# mother1.net
KiCad netlist of a schematic drawn in Altium Designer
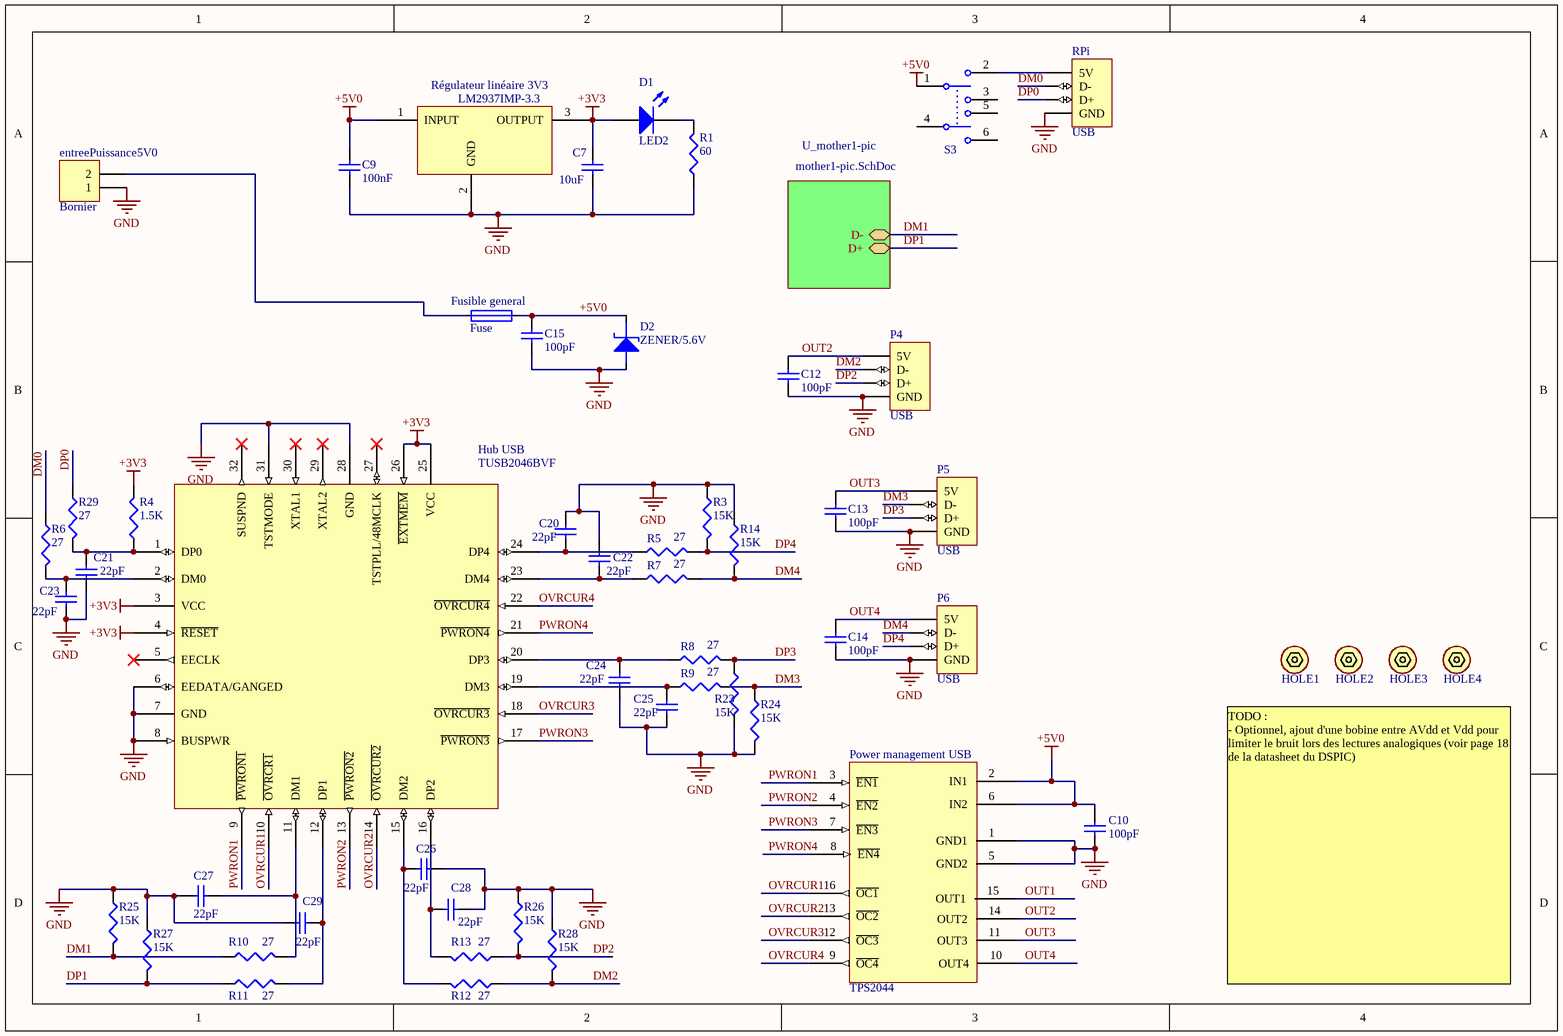
[diagram p0: mother1.SchDoc]

(export (version "E")
  (design (tool "Eeschema 10.0.6"))
  (components
    (comp (ref "C7")
      (value "10uF")
      (footprint "C0805C")
      (description "Capacitor")
      (fields (field (name "Comment") "CAP") (field (name "PUBLISHER") "Altium Limited"))
      (libsource (lib "7Robot") (part "CAP"))
    )
    (comp (ref "C9")
      (value "100nF")
      (footprint "C0805C")
      (description "Capacitor")
      (fields (field (name "Comment") "CAP") (field (name "PUBLISHER") "Altium Limited"))
      (libsource (lib "7Robot") (part "CAP"))
    )
    (comp (ref "C10")
      (value "100pF")
      (footprint "C0805C")
      (description "Capacitor")
      (fields (field (name "Comment") "CAP") (field (name "PUBLISHER") "Altium Limited"))
      (libsource (lib "7Robot") (part "CAP"))
    )
    (comp (ref "C12")
      (value "100pF")
      (footprint "C0805C")
      (description "Capacitor")
      (fields (field (name "Comment") "CAP") (field (name "PUBLISHER") "Altium Limited"))
      (libsource (lib "7Robot") (part "CAP"))
    )
    (comp (ref "C13")
      (value "100pF")
      (footprint "C0805C")
      (description "Capacitor")
      (fields (field (name "Comment") "CAP") (field (name "PUBLISHER") "Altium Limited"))
      (libsource (lib "7Robot") (part "CAP"))
    )
    (comp (ref "C14")
      (value "100pF")
      (footprint "C0805C")
      (description "Capacitor")
      (fields (field (name "Comment") "CAP") (field (name "PUBLISHER") "Altium Limited"))
      (libsource (lib "7Robot") (part "CAP"))
    )
    (comp (ref "C15")
      (value "100pF")
      (footprint "C0805C")
      (description "Capacitor")
      (fields (field (name "Comment") "CAP") (field (name "PUBLISHER") "Altium Limited"))
      (libsource (lib "7Robot") (part "CAP"))
    )
    (comp (ref "C20")
      (value "22pF")
      (footprint "C0805C")
      (description "Capacitor")
      (fields (field (name "Comment") "CAP") (field (name "PUBLISHER") "Altium Limited"))
      (libsource (lib "7Robot") (part "CAP"))
    )
    (comp (ref "C21")
      (value "22pF")
      (footprint "C0805C")
      (description "Capacitor")
      (fields (field (name "Comment") "CAP") (field (name "PUBLISHER") "Altium Limited"))
      (libsource (lib "7Robot") (part "CAP"))
    )
    (comp (ref "C22")
      (value "22pF")
      (footprint "C0805C")
      (description "Capacitor")
      (fields (field (name "Comment") "CAP") (field (name "PUBLISHER") "Altium Limited"))
      (libsource (lib "7Robot") (part "CAP"))
    )
    (comp (ref "C23")
      (value "22pF")
      (footprint "C0805C")
      (description "Capacitor")
      (fields (field (name "Comment") "CAP") (field (name "PUBLISHER") "Altium Limited"))
      (libsource (lib "7Robot") (part "CAP"))
    )
    (comp (ref "C24")
      (value "22pF")
      (footprint "C0805C")
      (description "Capacitor")
      (fields (field (name "Comment") "CAP") (field (name "PUBLISHER") "Altium Limited"))
      (libsource (lib "7Robot") (part "CAP"))
    )
    (comp (ref "C25")
      (value "22pF")
      (footprint "C0805C")
      (description "Capacitor")
      (fields (field (name "Comment") "CAP") (field (name "PUBLISHER") "Altium Limited"))
      (libsource (lib "7Robot") (part "CAP"))
    )
    (comp (ref "C26")
      (value "22pF")
      (footprint "C0805C")
      (description "Capacitor")
      (fields (field (name "Comment") "CAP") (field (name "PUBLISHER") "Altium Limited"))
      (libsource (lib "7Robot") (part "CAP"))
    )
    (comp (ref "C27")
      (value "22pF")
      (footprint "C0805C")
      (description "Capacitor")
      (fields (field (name "Comment") "CAP") (field (name "PUBLISHER") "Altium Limited"))
      (libsource (lib "7Robot") (part "CAP"))
    )
    (comp (ref "C28")
      (value "22pF")
      (footprint "C0805C")
      (description "Capacitor")
      (fields (field (name "Comment") "CAP") (field (name "PUBLISHER") "Altium Limited"))
      (libsource (lib "7Robot") (part "CAP"))
    )
    (comp (ref "C29")
      (value "22pF")
      (footprint "C0805C")
      (description "Capacitor")
      (fields (field (name "Comment") "CAP") (field (name "PUBLISHER") "Altium Limited"))
      (libsource (lib "7Robot") (part "CAP"))
    )
    (comp (ref "D1")
      (value "LED2")
      (footprint "LED1206G")
      (description "Typical RED, GREEN, YELLOW, AMBER GaAs LED")
      (fields (field (name "PUBLISHER") "Altium Limited"))
      (libsource (lib "7Robot") (part "LED2"))
    )
    (comp (ref "D2")
      (value "ZENER/5.6V")
      (footprint "DSO-C2/X1.8")
      (description "ZENER")
      (libsource (lib "7Robot") (part "ZENER"))
    )
    (comp (ref "entreePuissance5V0")
      (value "Bornier")
      (footprint "Bornier male coude 2 voies")
      (description "Header, 2-Pin")
      (fields (field (name "PUBLISHER") "Altium Limited"))
      (libsource (lib "7Robot") (part "Header 2"))
    )
    (comp (ref "Fusible general")
      (value "Fuse")
      (footprint "Fuse Holder 5x20mm")
      (libsource (lib "7Robot") (part "FUSE"))
    )
    (comp (ref "HOLE1")
      (value "Hole")
      (footprint "SCREW")
      (description "Mounting Hole for screws")
      (libsource (lib "7Robot") (part "Hole"))
    )
    (comp (ref "HOLE2")
      (value "Hole")
      (footprint "SCREW")
      (description "Mounting Hole for screws")
      (libsource (lib "7Robot") (part "Hole"))
    )
    (comp (ref "HOLE3")
      (value "Hole")
      (footprint "SCREW")
      (description "Mounting Hole for screws")
      (libsource (lib "7Robot") (part "Hole"))
    )
    (comp (ref "HOLE4")
      (value "Hole")
      (footprint "SCREW")
      (description "Mounting Hole for screws")
      (libsource (lib "7Robot") (part "Hole"))
    )
    (comp (ref "Hub USB")
      (value "TUSB2046BVF")
      (footprint "TUSB2046BVF")
      (description "TI 4-Port USB Hub")
      (libsource (lib "7Robot") (part "TUSB2046BVF"))
    )
    (comp (ref "P4")
      (value "USB")
      (footprint "USB SM female vertical")
      (description "USB Connector")
      (fields (field (name "PUBLISHER") "Altium Limited"))
      (libsource (lib "7Robot") (part "USB Con"))
    )
    (comp (ref "P5")
      (value "USB")
      (footprint "USB SM female vertical")
      (description "USB Connector")
      (fields (field (name "PUBLISHER") "Altium Limited"))
      (libsource (lib "7Robot") (part "USB Con"))
    )
    (comp (ref "P6")
      (value "USB")
      (footprint "USB SM female vertical")
      (description "USB Connector")
      (fields (field (name "PUBLISHER") "Altium Limited"))
      (libsource (lib "7Robot") (part "USB Con"))
    )
    (comp (ref "Power management USB")
      (value "TPS2044")
      (footprint "TPS2044")
      (description "Power distribution USB")
      (libsource (lib "7Robot") (part "TPS2044"))
    )
    (comp (ref "R1")
      (value "60")
      (footprint "C0805R")
      (description "Resistor")
      (fields (field (name "Comment") "RES") (field (name "PUBLISHER") "Altium Limited"))
      (libsource (lib "7Robot") (part "RES"))
    )
    (comp (ref "R3")
      (value "15K")
      (footprint "C0805R")
      (description "Resistor")
      (fields (field (name "Comment") "RES") (field (name "PUBLISHER") "Altium Limited"))
      (libsource (lib "7Robot") (part "RES"))
    )
    (comp (ref "R4")
      (value "1.5K")
      (footprint "C0805R")
      (description "Resistor")
      (fields (field (name "Comment") "RES") (field (name "PUBLISHER") "Altium Limited"))
      (libsource (lib "7Robot") (part "RES"))
    )
    (comp (ref "R5")
      (value "27")
      (footprint "C0805R")
      (description "Resistor")
      (fields (field (name "Comment") "RES") (field (name "PUBLISHER") "Altium Limited"))
      (libsource (lib "7Robot") (part "RES"))
    )
    (comp (ref "R6")
      (value "27")
      (footprint "C0805R")
      (description "Resistor")
      (fields (field (name "Comment") "RES") (field (name "PUBLISHER") "Altium Limited"))
      (libsource (lib "7Robot") (part "RES"))
    )
    (comp (ref "R7")
      (value "27")
      (footprint "C0805R")
      (description "Resistor")
      (fields (field (name "Comment") "RES") (field (name "PUBLISHER") "Altium Limited"))
      (libsource (lib "7Robot") (part "RES"))
    )
    (comp (ref "R8")
      (value "27")
      (footprint "C0805R")
      (description "Resistor")
      (fields (field (name "Comment") "RES") (field (name "PUBLISHER") "Altium Limited"))
      (libsource (lib "7Robot") (part "RES"))
    )
    (comp (ref "R9")
      (value "27")
      (footprint "C0805R")
      (description "Resistor")
      (fields (field (name "Comment") "RES") (field (name "PUBLISHER") "Altium Limited"))
      (libsource (lib "7Robot") (part "RES"))
    )
    (comp (ref "R10")
      (value "27")
      (footprint "C0805R")
      (description "Resistor")
      (fields (field (name "Comment") "RES") (field (name "PUBLISHER") "Altium Limited"))
      (libsource (lib "7Robot") (part "RES"))
    )
    (comp (ref "R11")
      (value "27")
      (footprint "C0805R")
      (description "Resistor")
      (fields (field (name "Comment") "RES") (field (name "PUBLISHER") "Altium Limited"))
      (libsource (lib "7Robot") (part "RES"))
    )
    (comp (ref "R12")
      (value "27")
      (footprint "C0805R")
      (description "Resistor")
      (fields (field (name "Comment") "RES") (field (name "PUBLISHER") "Altium Limited"))
      (libsource (lib "7Robot") (part "RES"))
    )
    (comp (ref "R13")
      (value "27")
      (footprint "C0805R")
      (description "Resistor")
      (fields (field (name "Comment") "RES") (field (name "PUBLISHER") "Altium Limited"))
      (libsource (lib "7Robot") (part "RES"))
    )
    (comp (ref "R14")
      (value "15K")
      (footprint "C0805R")
      (description "Resistor")
      (fields (field (name "Comment") "RES") (field (name "PUBLISHER") "Altium Limited"))
      (libsource (lib "7Robot") (part "RES"))
    )
    (comp (ref "R23")
      (value "15K")
      (footprint "C0805R")
      (description "Resistor")
      (fields (field (name "Comment") "RES") (field (name "PUBLISHER") "Altium Limited"))
      (libsource (lib "7Robot") (part "RES"))
    )
    (comp (ref "R24")
      (value "15K")
      (footprint "C0805R")
      (description "Resistor")
      (fields (field (name "Comment") "RES") (field (name "PUBLISHER") "Altium Limited"))
      (libsource (lib "7Robot") (part "RES"))
    )
    (comp (ref "R25")
      (value "15K")
      (footprint "C0805R")
      (description "Resistor")
      (fields (field (name "Comment") "RES") (field (name "PUBLISHER") "Altium Limited"))
      (libsource (lib "7Robot") (part "RES"))
    )
    (comp (ref "R26")
      (value "15K")
      (footprint "C0805R")
      (description "Resistor")
      (fields (field (name "Comment") "RES") (field (name "PUBLISHER") "Altium Limited"))
      (libsource (lib "7Robot") (part "RES"))
    )
    (comp (ref "R27")
      (value "15K")
      (footprint "C0805R")
      (description "Resistor")
      (fields (field (name "Comment") "RES") (field (name "PUBLISHER") "Altium Limited"))
      (libsource (lib "7Robot") (part "RES"))
    )
    (comp (ref "R28")
      (value "15K")
      (footprint "C0805R")
      (description "Resistor")
      (fields (field (name "Comment") "RES") (field (name "PUBLISHER") "Altium Limited"))
      (libsource (lib "7Robot") (part "RES"))
    )
    (comp (ref "R29")
      (value "27")
      (footprint "C0805R")
      (description "Resistor")
      (fields (field (name "Comment") "RES") (field (name "PUBLISHER") "Altium Limited"))
      (libsource (lib "7Robot") (part "RES"))
    )
    (comp (ref "RPi")
      (value "USB")
      (footprint "USB SM2.5 Male")
      (description "USB Connector")
      (fields (field (name "PUBLISHER") "Altium Limited"))
      (libsource (lib "7Robot") (part "USB Con"))
    )
    (comp (ref "Régulateur linéaire 3V3")
      (value "LM2937IMP-3.3")
      (footprint "SOT223")
      (description "500 mA Low Dropout Regulator")
      (libsource (lib "7Robot") (part "LM2937IMP-3.3"))
    )
    (comp (ref "S3")
      (value "SW-DPDT/Reset")
      (footprint "MCLSS22")
      (description "Double-Pole, Double-Throw Switch, ref MCLSS22")
      (fields (field (name "PUBLISHER") "Altium Limited"))
      (libsource (lib "7Robot") (part "SW-DPDT"))
    )
  )
  (nets
    (net (code "1") (name "+3V3") (class "Default")
      (node (ref "C7") (pin "2") (pinfunction "2_2") (pintype "passive"))
      (node (ref "D1") (pin "1") (pinfunction "A_1") (pintype "passive"))
      (node (ref "Hub USB") (pin "25") (pinfunction "VCC_25") (pintype "power_in"))
      (node (ref "Hub USB") (pin "26") (pinfunction "~{EXTMEM}_26") (pintype "input"))
      (node (ref "Hub USB") (pin "3") (pinfunction "VCC_3") (pintype "power_in"))
      (node (ref "Hub USB") (pin "4") (pinfunction "~{RESET}_4") (pintype "input"))
      (node (ref "R4") (pin "2") (pinfunction "2_2") (pintype "passive"))
      (node (ref "Régulateur linéaire 3V3") (pin "3") (pinfunction "OUTPUT_3") (pintype "power_in"))
    )
    (net (code "2") (name "+5V0") (class "Default")
      (node (ref "C10") (pin "1") (pinfunction "1_1") (pintype "passive"))
      (node (ref "C15") (pin "2") (pinfunction "2_2") (pintype "passive"))
      (node (ref "C9") (pin "1") (pinfunction "1_1") (pintype "passive"))
      (node (ref "D2") (pin "K") (pinfunction "K_K") (pintype "passive"))
      (node (ref "Fusible general") (pin "2") (pinfunction "2_2") (pintype "passive"))
      (node (ref "Power management USB") (pin "2") (pinfunction "IN1_2") (pintype "passive"))
      (node (ref "Power management USB") (pin "6") (pinfunction "IN2_6") (pintype "passive"))
      (node (ref "Régulateur linéaire 3V3") (pin "1") (pinfunction "INPUT_1") (pintype "power_in"))
      (node (ref "S3") (pin "1") (pinfunction "1_1") (pintype "passive"))
    )
    (net (code "3") (name "/DM0") (class "Default")
      (node (ref "R6") (pin "1") (pinfunction "1_1") (pintype "passive"))
      (node (ref "RPi") (pin "2") (pinfunction "D-_2") (pintype "bidirectional"))
    )
    (net (code "4") (name "/DM1") (class "Default")
      (node (ref "R10") (pin "1") (pinfunction "1_1") (pintype "passive"))
      (node (ref "R25") (pin "2") (pinfunction "2_2") (pintype "passive"))
    )
    (net (code "5") (name "/DM2") (class "Default")
      (node (ref "P4") (pin "2") (pinfunction "D-_2") (pintype "bidirectional"))
      (node (ref "R12") (pin "1") (pinfunction "1_1") (pintype "passive"))
      (node (ref "R28") (pin "2") (pinfunction "2_2") (pintype "passive"))
    )
    (net (code "6") (name "/DM3") (class "Default")
      (node (ref "P5") (pin "2") (pinfunction "D-_2") (pintype "bidirectional"))
      (node (ref "R24") (pin "1") (pinfunction "1_1") (pintype "passive"))
      (node (ref "R9") (pin "2") (pinfunction "2_2") (pintype "passive"))
    )
    (net (code "7") (name "/DM4") (class "Default")
      (node (ref "P6") (pin "2") (pinfunction "D-_2") (pintype "bidirectional"))
      (node (ref "R14") (pin "2") (pinfunction "2_2") (pintype "passive"))
      (node (ref "R7") (pin "2") (pinfunction "2_2") (pintype "passive"))
    )
    (net (code "8") (name "/DP0") (class "Default")
      (node (ref "R29") (pin "1") (pinfunction "1_1") (pintype "passive"))
      (node (ref "RPi") (pin "3") (pinfunction "D+_3") (pintype "bidirectional"))
    )
    (net (code "9") (name "/DP1") (class "Default")
      (node (ref "R11") (pin "1") (pinfunction "1_1") (pintype "passive"))
      (node (ref "R27") (pin "2") (pinfunction "2_2") (pintype "passive"))
    )
    (net (code "10") (name "/DP2") (class "Default")
      (node (ref "P4") (pin "3") (pinfunction "D+_3") (pintype "bidirectional"))
      (node (ref "R13") (pin "1") (pinfunction "1_1") (pintype "passive"))
      (node (ref "R26") (pin "2") (pinfunction "2_2") (pintype "passive"))
    )
    (net (code "11") (name "/DP3") (class "Default")
      (node (ref "P5") (pin "3") (pinfunction "D+_3") (pintype "bidirectional"))
      (node (ref "R23") (pin "1") (pinfunction "1_1") (pintype "passive"))
      (node (ref "R8") (pin "2") (pinfunction "2_2") (pintype "passive"))
    )
    (net (code "12") (name "/DP4") (class "Default")
      (node (ref "P6") (pin "3") (pinfunction "D+_3") (pintype "bidirectional"))
      (node (ref "R3") (pin "2") (pinfunction "2_2") (pintype "passive"))
      (node (ref "R5") (pin "2") (pinfunction "2_2") (pintype "passive"))
    )
    (net (code "13") (name "/OUT1") (class "Default")
      (node (ref "Power management USB") (pin "15") (pinfunction "OUT1_15") (pintype "power_in"))
    )
    (net (code "14") (name "/OUT2") (class "Default")
      (node (ref "C12") (pin "2") (pinfunction "2_2") (pintype "passive"))
      (node (ref "P4") (pin "1") (pinfunction "5V_1") (pintype "power_in"))
      (node (ref "Power management USB") (pin "14") (pinfunction "OUT2_14") (pintype "power_in"))
    )
    (net (code "15") (name "/OUT3") (class "Default")
      (node (ref "C13") (pin "2") (pinfunction "2_2") (pintype "passive"))
      (node (ref "P5") (pin "1") (pinfunction "5V_1") (pintype "power_in"))
      (node (ref "Power management USB") (pin "11") (pinfunction "OUT3_11") (pintype "power_in"))
    )
    (net (code "16") (name "/OUT4") (class "Default")
      (node (ref "C14") (pin "2") (pinfunction "2_2") (pintype "passive"))
      (node (ref "P6") (pin "1") (pinfunction "5V_1") (pintype "power_in"))
      (node (ref "Power management USB") (pin "10") (pinfunction "OUT4_10") (pintype "power_in"))
    )
    (net (code "17") (name "/OVRCUR1") (class "Default")
      (node (ref "Hub USB") (pin "10") (pinfunction "~{OVRCR1}_10") (pintype "input"))
      (node (ref "Power management USB") (pin "16") (pinfunction "~{OC1}_16") (pintype "output"))
    )
    (net (code "18") (name "/OVRCUR2") (class "Default")
      (node (ref "Hub USB") (pin "14") (pinfunction "~{OVRCUR2}_14") (pintype "input"))
      (node (ref "Power management USB") (pin "13") (pinfunction "~{OC2}_13") (pintype "output"))
    )
    (net (code "19") (name "/OVRCUR3") (class "Default")
      (node (ref "Hub USB") (pin "18") (pinfunction "~{OVRCUR3}_18") (pintype "input"))
      (node (ref "Power management USB") (pin "12") (pinfunction "~{OC3}_12") (pintype "output"))
    )
    (net (code "20") (name "/OVRCUR4") (class "Default")
      (node (ref "Hub USB") (pin "22") (pinfunction "~{OVRCUR4}_22") (pintype "input"))
      (node (ref "Power management USB") (pin "9") (pinfunction "~{OC4}_9") (pintype "output"))
    )
    (net (code "21") (name "/PWRON1") (class "Default")
      (node (ref "Hub USB") (pin "9") (pinfunction "~{PWRON1}_9") (pintype "output"))
      (node (ref "Power management USB") (pin "3") (pinfunction "~{EN1}_3") (pintype "input"))
    )
    (net (code "22") (name "/PWRON2") (class "Default")
      (node (ref "Hub USB") (pin "13") (pinfunction "~{PWRON2}_13") (pintype "output"))
      (node (ref "Power management USB") (pin "4") (pinfunction "~{EN2}_4") (pintype "input"))
    )
    (net (code "23") (name "/PWRON3") (class "Default")
      (node (ref "Hub USB") (pin "17") (pinfunction "~{PWRON3}_17") (pintype "output"))
      (node (ref "Power management USB") (pin "7") (pinfunction "~{EN3}_7") (pintype "input"))
    )
    (net (code "24") (name "/PWRON4") (class "Default")
      (node (ref "Hub USB") (pin "21") (pinfunction "~{PWRON4}_21") (pintype "output"))
      (node (ref "Power management USB") (pin "8") (pinfunction "~{EN4}_8") (pintype "input"))
    )
    (net (code "25") (name "GND") (class "Default")
      (node (ref "C10") (pin "2") (pinfunction "2_2") (pintype "passive"))
      (node (ref "C12") (pin "1") (pinfunction "1_1") (pintype "passive"))
      (node (ref "C13") (pin "1") (pinfunction "1_1") (pintype "passive"))
      (node (ref "C14") (pin "1") (pinfunction "1_1") (pintype "passive"))
      (node (ref "C15") (pin "1") (pinfunction "1_1") (pintype "passive"))
      (node (ref "C20") (pin "2") (pinfunction "2_2") (pintype "passive"))
      (node (ref "C21") (pin "2") (pinfunction "2_2") (pintype "passive"))
      (node (ref "C22") (pin "2") (pinfunction "2_2") (pintype "passive"))
      (node (ref "C23") (pin "2") (pinfunction "2_2") (pintype "passive"))
      (node (ref "C24") (pin "1") (pinfunction "1_1") (pintype "passive"))
      (node (ref "C25") (pin "1") (pinfunction "1_1") (pintype "passive"))
      (node (ref "C26") (pin "1") (pinfunction "1_1") (pintype "passive"))
      (node (ref "C27") (pin "2") (pinfunction "2_2") (pintype "passive"))
      (node (ref "C28") (pin "1") (pinfunction "1_1") (pintype "passive"))
      (node (ref "C29") (pin "1") (pinfunction "1_1") (pintype "passive"))
      (node (ref "C7") (pin "1") (pinfunction "1_1") (pintype "passive"))
      (node (ref "C9") (pin "2") (pinfunction "2_2") (pintype "passive"))
      (node (ref "D2") (pin "A") (pinfunction "A_A") (pintype "passive"))
      (node (ref "Hub USB") (pin "28") (pinfunction "GND_28") (pintype "power_in"))
      (node (ref "Hub USB") (pin "31") (pinfunction "TSTMODE_31") (pintype "input"))
      (node (ref "Hub USB") (pin "6") (pinfunction "EEDATA/GANGED_6") (pintype "bidirectional"))
      (node (ref "Hub USB") (pin "7") (pinfunction "GND_7") (pintype "power_in"))
      (node (ref "Hub USB") (pin "8") (pinfunction "BUSPWR_8") (pintype "input"))
      (node (ref "P4") (pin "4") (pinfunction "GND_4") (pintype "power_in"))
      (node (ref "P5") (pin "4") (pinfunction "GND_4") (pintype "power_in"))
      (node (ref "P6") (pin "4") (pinfunction "GND_4") (pintype "power_in"))
      (node (ref "Power management USB") (pin "1") (pinfunction "GND1_1") (pintype "passive"))
      (node (ref "Power management USB") (pin "5") (pinfunction "GND2_5") (pintype "passive"))
      (node (ref "R1") (pin "1") (pinfunction "1_1") (pintype "passive"))
      (node (ref "R14") (pin "1") (pinfunction "1_1") (pintype "passive"))
      (node (ref "R23") (pin "2") (pinfunction "2_2") (pintype "passive"))
      (node (ref "R24") (pin "2") (pinfunction "2_2") (pintype "passive"))
      (node (ref "R25") (pin "1") (pinfunction "1_1") (pintype "passive"))
      (node (ref "R26") (pin "1") (pinfunction "1_1") (pintype "passive"))
      (node (ref "R27") (pin "1") (pinfunction "1_1") (pintype "passive"))
      (node (ref "R28") (pin "1") (pinfunction "1_1") (pintype "passive"))
      (node (ref "R3") (pin "1") (pinfunction "1_1") (pintype "passive"))
      (node (ref "RPi") (pin "4") (pinfunction "GND_4") (pintype "power_in"))
      (node (ref "Régulateur linéaire 3V3") (pin "2") (pinfunction "GND_2") (pintype "power_in"))
      (node (ref "entreePuissance5V0") (pin "1") (pinfunction "1_1") (pintype "passive"))
    )
    (net (code "26") (name "Net-(D1-K)") (class "Default")
      (node (ref "D1") (pin "2") (pinfunction "K_2") (pintype "passive"))
      (node (ref "R1") (pin "2") (pinfunction "2_2") (pintype "passive"))
    )
    (net (code "27") (name "Net-(Fusible general-Pad1)") (class "Default")
      (node (ref "Fusible general") (pin "1") (pinfunction "1_1") (pintype "passive"))
      (node (ref "entreePuissance5V0") (pin "2") (pinfunction "2_2") (pintype "passive"))
    )
    (net (code "28") (name "Net-(Hub USB-DM0)") (class "Default")
      (node (ref "C23") (pin "1") (pinfunction "1_1") (pintype "passive"))
      (node (ref "Hub USB") (pin "2") (pinfunction "DM0_2") (pintype "bidirectional"))
      (node (ref "R6") (pin "2") (pinfunction "2_2") (pintype "passive"))
    )
    (net (code "29") (name "Net-(Hub USB-DM1)") (class "Default")
      (node (ref "C27") (pin "1") (pinfunction "1_1") (pintype "passive"))
      (node (ref "Hub USB") (pin "11") (pinfunction "DM1_11") (pintype "bidirectional"))
      (node (ref "R10") (pin "2") (pinfunction "2_2") (pintype "passive"))
    )
    (net (code "30") (name "Net-(Hub USB-DM2)") (class "Default")
      (node (ref "C26") (pin "2") (pinfunction "2_2") (pintype "passive"))
      (node (ref "Hub USB") (pin "15") (pinfunction "DM2_15") (pintype "bidirectional"))
      (node (ref "R12") (pin "2") (pinfunction "2_2") (pintype "passive"))
    )
    (net (code "31") (name "Net-(Hub USB-DM3)") (class "Default")
      (node (ref "C25") (pin "2") (pinfunction "2_2") (pintype "passive"))
      (node (ref "Hub USB") (pin "19") (pinfunction "DM3_19") (pintype "bidirectional"))
      (node (ref "R9") (pin "1") (pinfunction "1_1") (pintype "passive"))
    )
    (net (code "32") (name "Net-(Hub USB-DM4)") (class "Default")
      (node (ref "C22") (pin "1") (pinfunction "1_1") (pintype "passive"))
      (node (ref "Hub USB") (pin "23") (pinfunction "DM4_23") (pintype "bidirectional"))
      (node (ref "R7") (pin "1") (pinfunction "1_1") (pintype "passive"))
    )
    (net (code "33") (name "Net-(Hub USB-DP0)") (class "Default")
      (node (ref "C21") (pin "1") (pinfunction "1_1") (pintype "passive"))
      (node (ref "Hub USB") (pin "1") (pinfunction "DP0_1") (pintype "bidirectional"))
      (node (ref "R29") (pin "2") (pinfunction "2_2") (pintype "passive"))
      (node (ref "R4") (pin "1") (pinfunction "1_1") (pintype "passive"))
    )
    (net (code "34") (name "Net-(Hub USB-DP1)") (class "Default")
      (node (ref "C29") (pin "2") (pinfunction "2_2") (pintype "passive"))
      (node (ref "Hub USB") (pin "12") (pinfunction "DP1_12") (pintype "bidirectional"))
      (node (ref "R11") (pin "2") (pinfunction "2_2") (pintype "passive"))
    )
    (net (code "35") (name "Net-(Hub USB-DP2)") (class "Default")
      (node (ref "C28") (pin "2") (pinfunction "2_2") (pintype "passive"))
      (node (ref "Hub USB") (pin "16") (pinfunction "DP2_16") (pintype "bidirectional"))
      (node (ref "R13") (pin "2") (pinfunction "2_2") (pintype "passive"))
    )
    (net (code "36") (name "Net-(Hub USB-DP3)") (class "Default")
      (node (ref "C24") (pin "2") (pinfunction "2_2") (pintype "passive"))
      (node (ref "Hub USB") (pin "20") (pinfunction "DP3_20") (pintype "bidirectional"))
      (node (ref "R8") (pin "1") (pinfunction "1_1") (pintype "passive"))
    )
    (net (code "37") (name "Net-(Hub USB-DP4)") (class "Default")
      (node (ref "C20") (pin "1") (pinfunction "1_1") (pintype "passive"))
      (node (ref "Hub USB") (pin "24") (pinfunction "DP4_24") (pintype "bidirectional"))
      (node (ref "R5") (pin "1") (pinfunction "1_1") (pintype "passive"))
    )
    (net (code "38") (name "Net-(RPi-5V)") (class "Default")
      (node (ref "RPi") (pin "1") (pinfunction "5V_1") (pintype "power_in"))
      (node (ref "S3") (pin "2") (pinfunction "2_2") (pintype "passive"))
    )
    (net (code "39") (name "unconnected-(HOLE1-Hole-Pad1)") (class "Default")
      (node (ref "HOLE1") (pin "1") (pinfunction "Hole_1") (pintype "passive"))
    )
    (net (code "40") (name "unconnected-(HOLE2-Hole-Pad1)") (class "Default")
      (node (ref "HOLE2") (pin "1") (pinfunction "Hole_1") (pintype "passive"))
    )
    (net (code "41") (name "unconnected-(HOLE3-Hole-Pad1)") (class "Default")
      (node (ref "HOLE3") (pin "1") (pinfunction "Hole_1") (pintype "passive"))
    )
    (net (code "42") (name "unconnected-(HOLE4-Hole-Pad1)") (class "Default")
      (node (ref "HOLE4") (pin "1") (pinfunction "Hole_1") (pintype "passive"))
    )
    (net (code "43") (name "unconnected-(Hub USB-EECLK-Pad5)") (class "Default")
      (node (ref "Hub USB") (pin "5") (pinfunction "EECLK_5") (pintype "output+no_connect"))
    )
    (net (code "44") (name "unconnected-(Hub USB-SUSPND-Pad32)") (class "Default")
      (node (ref "Hub USB") (pin "32") (pinfunction "SUSPND_32") (pintype "output+no_connect"))
    )
    (net (code "45") (name "unconnected-(Hub USB-TSTPLL{slash}48MCLK-Pad27)") (class "Default")
      (node (ref "Hub USB") (pin "27") (pinfunction "TSTPLL/48MCLK_27") (pintype "bidirectional+no_connect"))
    )
    (net (code "46") (name "unconnected-(Hub USB-XTAL1-Pad30)") (class "Default")
      (node (ref "Hub USB") (pin "30") (pinfunction "XTAL1_30") (pintype "input+no_connect"))
    )
    (net (code "47") (name "unconnected-(Hub USB-XTAL2-Pad29)") (class "Default")
      (node (ref "Hub USB") (pin "29") (pinfunction "XTAL2_29") (pintype "output+no_connect"))
    )
    (net (code "48") (name "unconnected-(S3-Pad3)") (class "Default")
      (node (ref "S3") (pin "3") (pinfunction "3_3") (pintype "passive"))
    )
    (net (code "49") (name "unconnected-(S3-Pad4)") (class "Default")
      (node (ref "S3") (pin "4") (pinfunction "4_4") (pintype "passive"))
    )
    (net (code "50") (name "unconnected-(S3-Pad5)") (class "Default")
      (node (ref "S3") (pin "5") (pinfunction "5_5") (pintype "passive"))
    )
    (net (code "51") (name "unconnected-(S3-Pad6)") (class "Default")
      (node (ref "S3") (pin "6") (pinfunction "6_6") (pintype "passive"))
    )
  )
)
